# 214.net
KiCad netlist of a schematic drawn in EasyEDA Pro
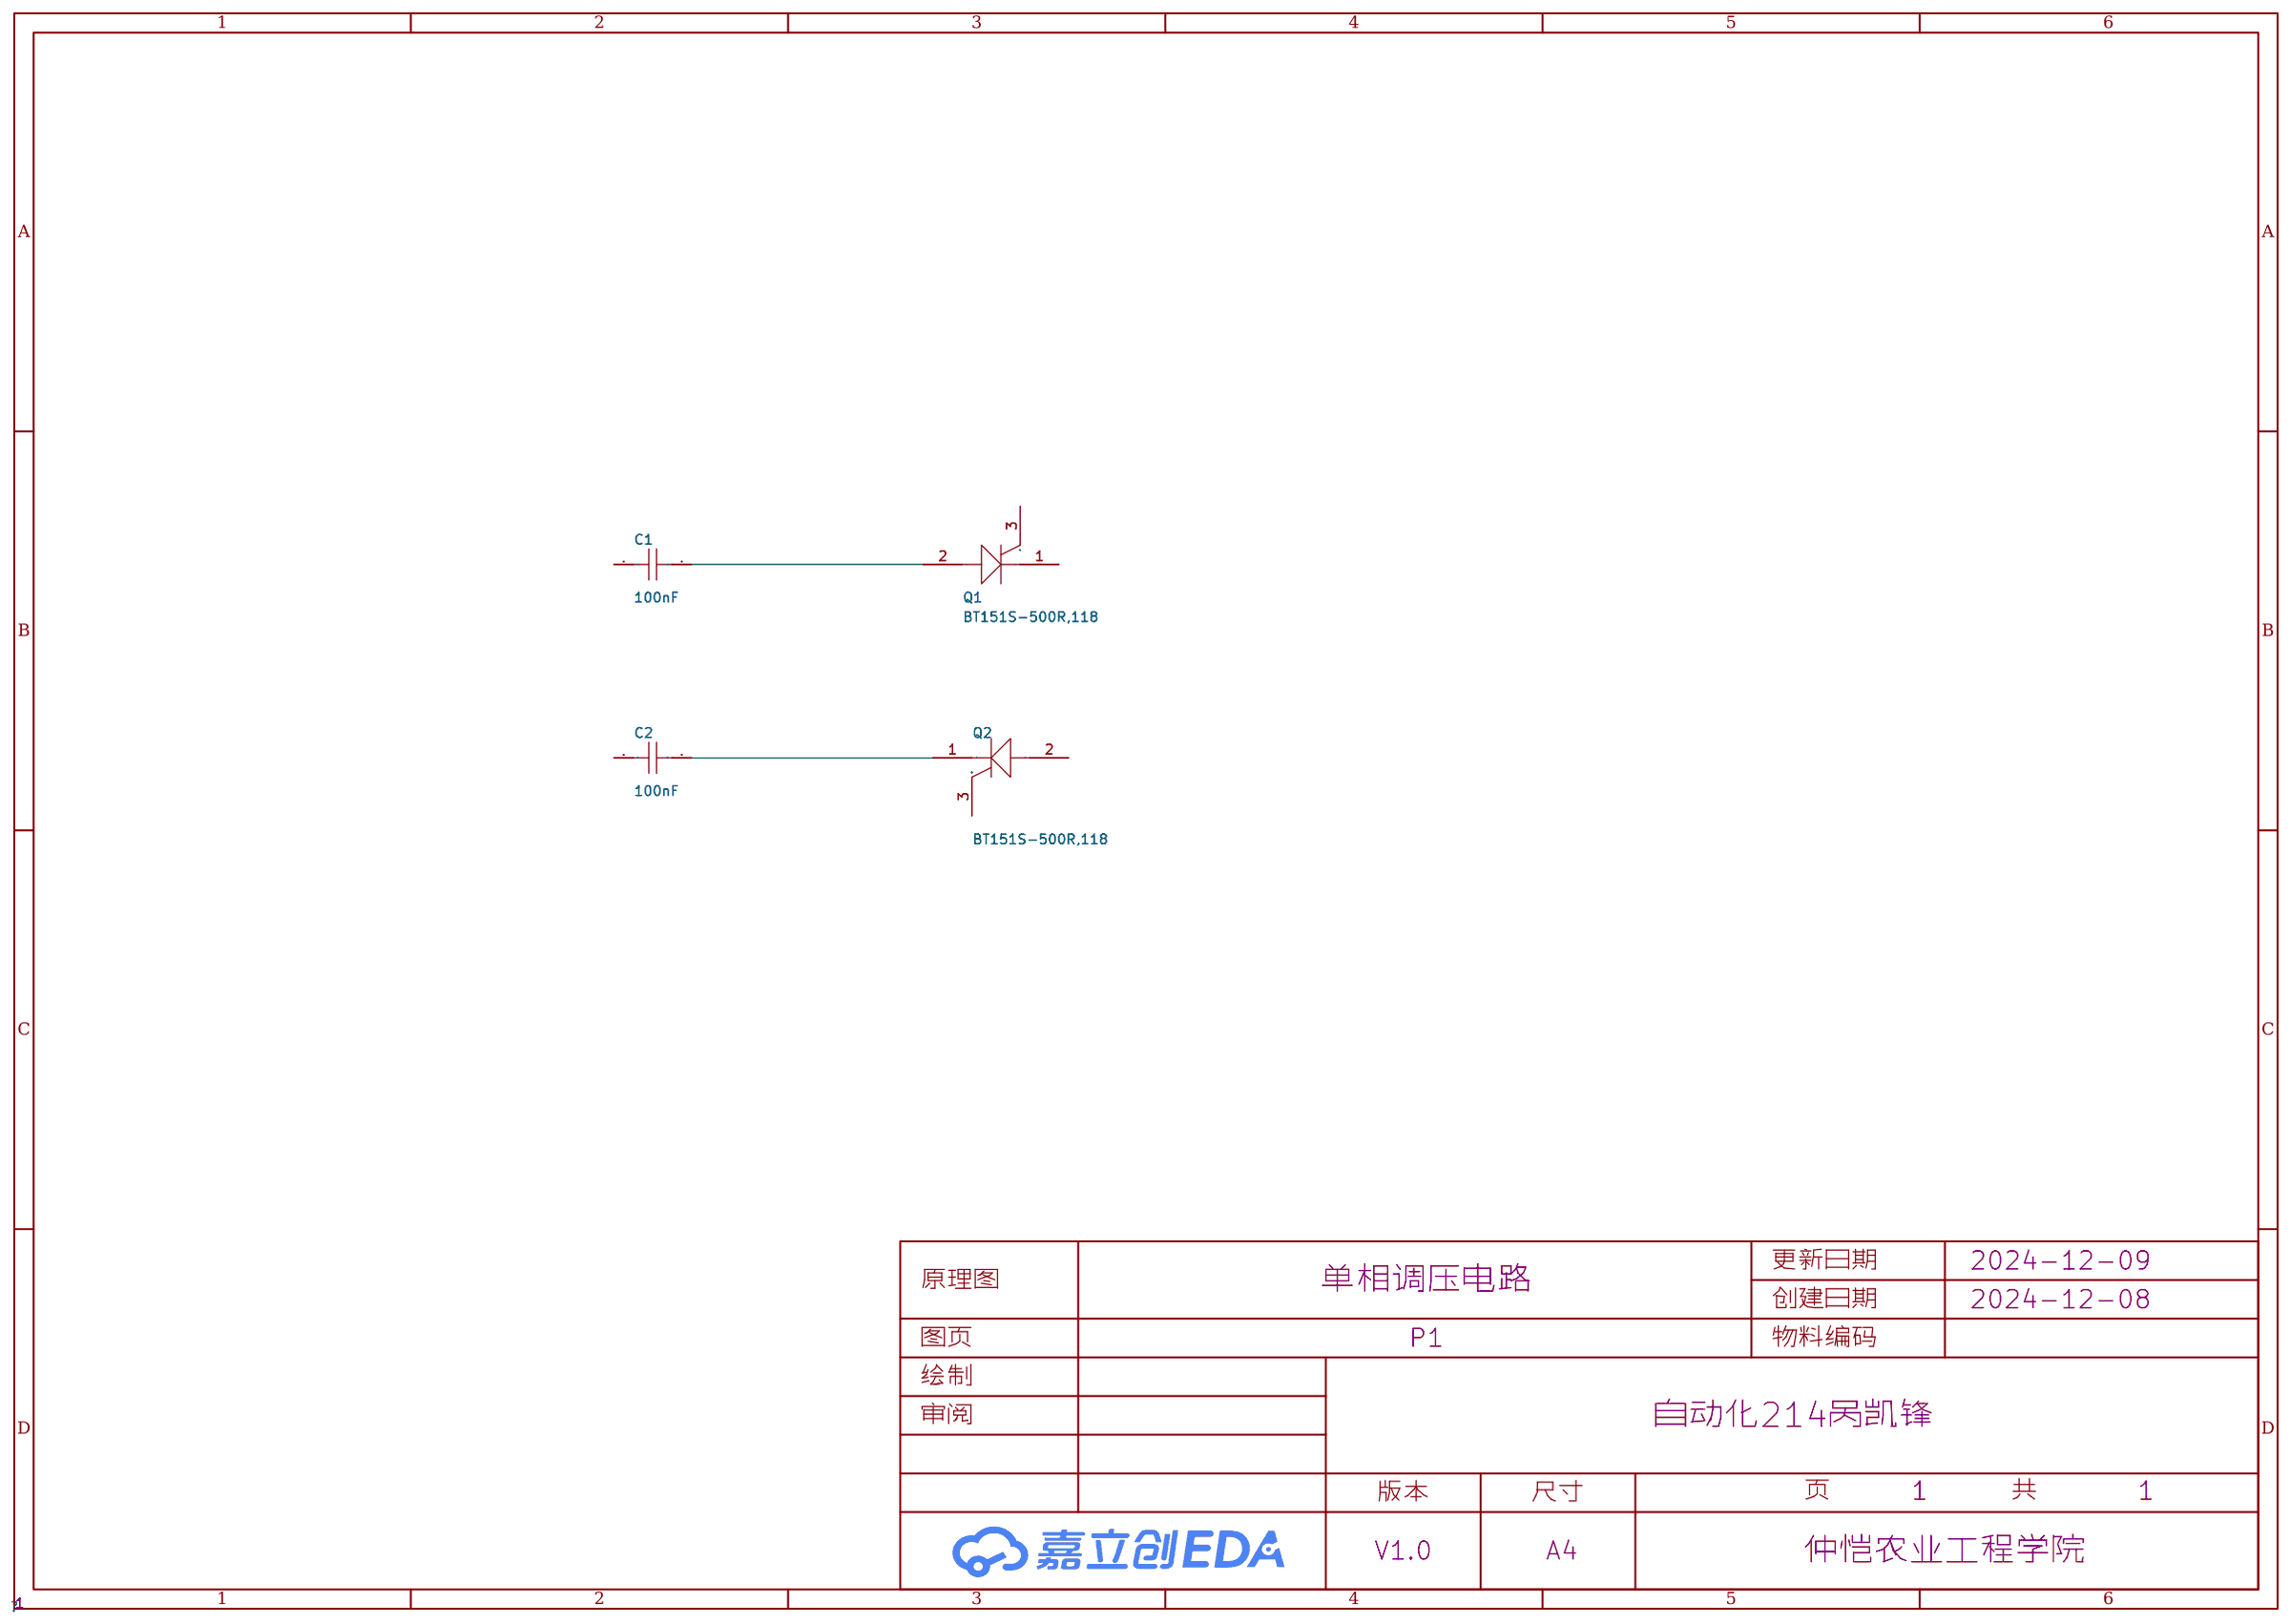
[diagram p0: schematic sheet]

(export (version "E")
  (design (tool "Eeschema 10.0.6"))
  (components
    (comp (ref "C1")
      (value "100nF")
      (footprint "easyedapro:C0603")
      (libsource (lib "easyedapro") (part "CapAcitance"))
    )
    (comp (ref "C2")
      (value "100nF")
      (footprint "easyedapro:C0603")
      (libsource (lib "easyedapro") (part "CapAcitance"))
    )
    (comp (ref "Q1")
      (value "BT151S-500R,118")
      (footprint "easyedapro:DPAK-3_L6.6-W6.1-P2.28-LS9.9-BR")
      (description "可控硅类型:1个单向可控硅;保持电流(Ih):20mA;断态峰值电压(Vdrm):500V;门极触发电流(Igt):15mA;")
      (fields (field (name "Manufacturer") "WeEn(瑞能)"))
      (libsource (lib "easyedapro") (part "BT151S-500R,118"))
    )
    (comp (ref "Q2")
      (value "BT151S-500R,118")
      (footprint "easyedapro:DPAK-3_L6.6-W6.1-P2.28-LS9.9-BR")
      (description "可控硅类型:1个单向可控硅;保持电流(Ih):20mA;断态峰值电压(Vdrm):500V;门极触发电流(Igt):15mA;")
      (fields (field (name "Manufacturer") "WeEn(瑞能)"))
      (libsource (lib "easyedapro") (part "BT151S-500R,118"))
    )
  )
  (nets
    (net (code "1") (name "Net-(Q1-A)") (class "Default")
      (node (ref "C1") (pin "2") (pinfunction "2_2") (pintype "input"))
      (node (ref "Q1") (pin "2") (pinfunction "A_2") (pintype "unspecified"))
    )
    (net (code "2") (name "Net-(Q2-K)") (class "Default")
      (node (ref "C2") (pin "2") (pinfunction "2_2") (pintype "input"))
      (node (ref "Q2") (pin "1") (pinfunction "K_1") (pintype "unspecified"))
    )
    (net (code "3") (name "unconnected-(C1-Pad1)") (class "Default")
      (node (ref "C1") (pin "1") (pinfunction "1_1") (pintype "input"))
    )
    (net (code "4") (name "unconnected-(C2-Pad1)") (class "Default")
      (node (ref "C2") (pin "1") (pinfunction "1_1") (pintype "input"))
    )
    (net (code "5") (name "unconnected-(Q1-G-Pad3)") (class "Default")
      (node (ref "Q1") (pin "3") (pinfunction "G_3") (pintype "unspecified"))
    )
    (net (code "6") (name "unconnected-(Q1-K-Pad1)") (class "Default")
      (node (ref "Q1") (pin "1") (pinfunction "K_1") (pintype "unspecified"))
    )
    (net (code "7") (name "unconnected-(Q2-A-Pad2)") (class "Default")
      (node (ref "Q2") (pin "2") (pinfunction "A_2") (pintype "unspecified"))
    )
    (net (code "8") (name "unconnected-(Q2-G-Pad3)") (class "Default")
      (node (ref "Q2") (pin "3") (pinfunction "G_3") (pintype "unspecified"))
    )
  )
)
